# Sheet4_LCD_Interface.net
KiCad netlist of a schematic drawn in Altium Designer
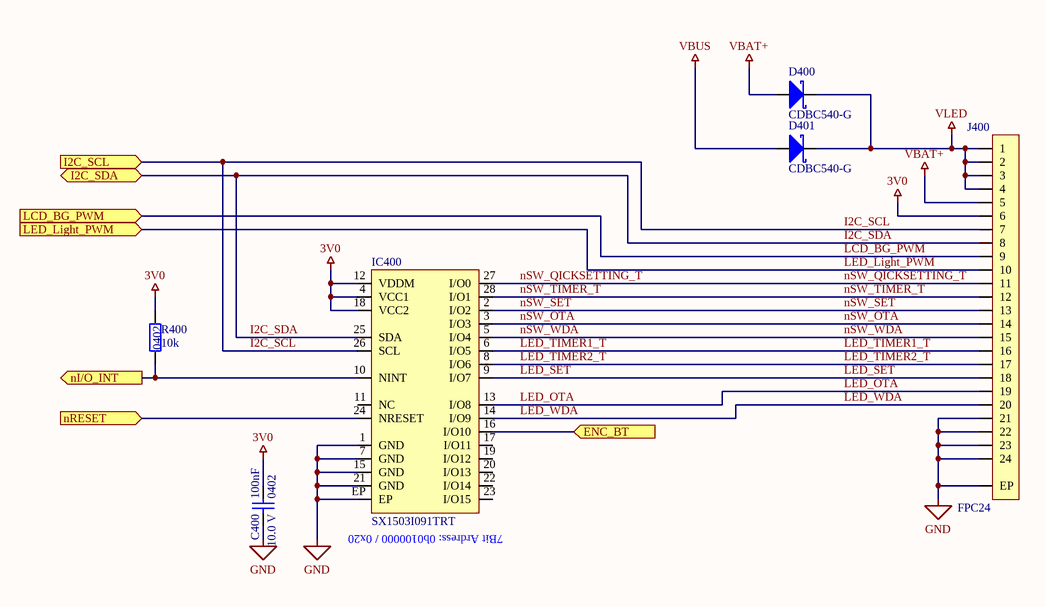
[diagram p0: Sheet4_LCD_Interface.SchDoc]

(export (version "E")
  (design (tool "Eeschema 10.0.6"))
  (components
    (comp (ref "C400")
      (value "C 100nF 0402 10V")
      (footprint "0402")
      (description "CAP CER 0.1UF 10V X5R 0402")
      (fields
        (field (name "MANUFACTURER") "Samsung Electro-Mechanics")
        (field (name "MANUFACTURER PART NUMBER") "CL05A104MP5NNNC")
        (field (name "CAPACITANCE") "100nF")
        (field (name "VOLTAGE") "10.0 V")
      )
      (libsource (lib "CS_Part_Library") (part "CAP_100nF_10V_0402"))
    )
    (comp (ref "D400")
      (value "D SCH 40V 5A")
      (footprint "DO-214AB")
      (description "DIODE SCHOTTKY 40V 5A DO214AB")
      (fields
        (field (name "MANUFACTURER") "Comchip Technology")
        (field (name "MANUFACTURER PART NUMBER") "CDBC540-G")
      )
      (libsource (lib "CS_Part_Library") (part "D_SCH_40V_5A"))
    )
    (comp (ref "D401")
      (value "D SCH 40V 5A")
      (footprint "DO-214AB")
      (description "DIODE SCHOTTKY 40V 5A DO214AB")
      (fields
        (field (name "MANUFACTURER") "Comchip Technology")
        (field (name "MANUFACTURER PART NUMBER") "CDBC540-G")
      )
      (libsource (lib "CS_Part_Library") (part "D_SCH_40V_5A"))
    )
    (comp (ref "IC400")
      (value "SX1503I091TRT")
      (footprint "UFQFN-28-EP")
      (description "IC GPIO EXPANDER I2C 16CH 28-QFN")
      (fields (field (name "MANUFACTURER") "Semtech Corporation"))
      (libsource (lib "CS_Part_Library") (part "IC_16ch_Port_Extender_2"))
    )
    (comp (ref "J400")
      (value "FPC24")
      (footprint "J_FPC_522712479")
      (description "CONN FPC BOT 24 PIN 1mm Pitch")
      (fields (field (name "MANUFACTURER") "MOLEX") (field (name "MANUFACTURER PART NUMBER") "522712479"))
      (libsource (lib "Symbols") (part "J_FPC24_DS"))
    )
    (comp (ref "R400")
      (value "R 10k 0402")
      (footprint "0402")
      (description "RES 10K OHM 1% 1/16W 0402")
      (fields
        (field (name "MANUFACTURER") "YAGEO")
        (field (name "MANUFACTURER PART NUMBER") "RC0402FR-0710KL")
        (field (name "RESISTANCE") "10k")
      )
      (libsource (lib "CS_Part_Library") (part "R_10k_0402"))
    )
  )
  (nets
    (net (code "1") (name "/ENC_BT") (class "Default")
      (node (ref "IC400") (pin "16") (pinfunction "I/O10_16") (pintype "passive"))
    )
    (net (code "2") (name "/I2C_SCL") (class "Default")
      (node (ref "IC400") (pin "26") (pinfunction "SCL_26") (pintype "passive"))
      (node (ref "J400") (pin "7") (pinfunction "7_7") (pintype "passive"))
    )
    (net (code "3") (name "/I2C_SDA") (class "Default")
      (node (ref "IC400") (pin "25") (pinfunction "SDA_25") (pintype "passive"))
      (node (ref "J400") (pin "8") (pinfunction "8_8") (pintype "passive"))
    )
    (net (code "4") (name "/LCD_BG_PWM") (class "Default")
      (node (ref "J400") (pin "9") (pinfunction "9_9") (pintype "passive"))
    )
    (net (code "5") (name "/LED_Light_PWM") (class "Default")
      (node (ref "J400") (pin "10") (pinfunction "10_10") (pintype "passive"))
    )
    (net (code "6") (name "/LED_OTA") (class "Default")
      (node (ref "IC400") (pin "13") (pinfunction "I/O8_13") (pintype "passive"))
      (node (ref "J400") (pin "19") (pinfunction "19_19") (pintype "passive"))
    )
    (net (code "7") (name "/LED_SET") (class "Default")
      (node (ref "IC400") (pin "9") (pinfunction "I/O7_9") (pintype "passive"))
      (node (ref "J400") (pin "18") (pinfunction "18_18") (pintype "passive"))
    )
    (net (code "8") (name "/LED_TIMER1_T") (class "Default")
      (node (ref "IC400") (pin "6") (pinfunction "I/O5_6") (pintype "passive"))
      (node (ref "J400") (pin "16") (pinfunction "16_16") (pintype "passive"))
    )
    (net (code "9") (name "/LED_TIMER2_T") (class "Default")
      (node (ref "IC400") (pin "8") (pinfunction "I/O6_8") (pintype "passive"))
      (node (ref "J400") (pin "17") (pinfunction "17_17") (pintype "passive"))
    )
    (net (code "10") (name "/LED_WDA") (class "Default")
      (node (ref "IC400") (pin "14") (pinfunction "I/O9_14") (pintype "passive"))
      (node (ref "J400") (pin "20") (pinfunction "20_20") (pintype "passive"))
    )
    (net (code "11") (name "/nI{slash}O_INT") (class "Default")
      (node (ref "IC400") (pin "10") (pinfunction "NINT_10") (pintype "passive"))
      (node (ref "R400") (pin "1") (pinfunction "1_1") (pintype "passive"))
    )
    (net (code "12") (name "/nRESET") (class "Default")
      (node (ref "IC400") (pin "24") (pinfunction "NRESET_24") (pintype "passive"))
    )
    (net (code "13") (name "/nSW_OTA") (class "Default")
      (node (ref "IC400") (pin "3") (pinfunction "I/O3_3") (pintype "passive"))
      (node (ref "J400") (pin "14") (pinfunction "14_14") (pintype "passive"))
    )
    (net (code "14") (name "/nSW_QICKSETTING_T") (class "Default")
      (node (ref "IC400") (pin "27") (pinfunction "I/O0_27") (pintype "passive"))
      (node (ref "J400") (pin "11") (pinfunction "11_11") (pintype "passive"))
    )
    (net (code "15") (name "/nSW_SET") (class "Default")
      (node (ref "IC400") (pin "2") (pinfunction "I/O2_2") (pintype "passive"))
      (node (ref "J400") (pin "13") (pinfunction "13_13") (pintype "passive"))
    )
    (net (code "16") (name "/nSW_TIMER_T") (class "Default")
      (node (ref "IC400") (pin "28") (pinfunction "I/O1_28") (pintype "passive"))
      (node (ref "J400") (pin "12") (pinfunction "12_12") (pintype "passive"))
    )
    (net (code "17") (name "/nSW_WDA") (class "Default")
      (node (ref "IC400") (pin "5") (pinfunction "I/O4_5") (pintype "passive"))
      (node (ref "J400") (pin "15") (pinfunction "15_15") (pintype "passive"))
    )
    (net (code "18") (name "3V0") (class "Default")
      (node (ref "C400") (pin "2") (pinfunction "2_2") (pintype "passive"))
      (node (ref "IC400") (pin "12") (pinfunction "VDDM_12") (pintype "passive"))
      (node (ref "IC400") (pin "18") (pinfunction "VCC2_18") (pintype "passive"))
      (node (ref "IC400") (pin "4") (pinfunction "VCC1_4") (pintype "passive"))
      (node (ref "J400") (pin "6") (pinfunction "6_6") (pintype "passive"))
      (node (ref "R400") (pin "2") (pinfunction "2_2") (pintype "passive"))
    )
    (net (code "19") (name "GND") (class "Default")
      (node (ref "C400") (pin "1") (pinfunction "1_1") (pintype "passive"))
      (node (ref "IC400") (pin "1") (pinfunction "GND_1") (pintype "passive"))
      (node (ref "IC400") (pin "15") (pinfunction "GND_15") (pintype "passive"))
      (node (ref "IC400") (pin "21") (pinfunction "GND_21") (pintype "passive"))
      (node (ref "IC400") (pin "7") (pinfunction "GND_7") (pintype "passive"))
      (node (ref "IC400") (pin "EP") (pinfunction "EP_EP") (pintype "passive"))
      (node (ref "J400") (pin "21") (pinfunction "21_21") (pintype "passive"))
      (node (ref "J400") (pin "22") (pinfunction "22_22") (pintype "passive"))
      (node (ref "J400") (pin "23") (pinfunction "23_23") (pintype "passive"))
      (node (ref "J400") (pin "24") (pinfunction "24_24") (pintype "passive"))
      (node (ref "J400") (pin "EP") (pinfunction "EP_EP") (pintype "passive"))
    )
    (net (code "20") (name "VBAT+") (class "Default")
      (node (ref "D400") (pin "2") (pinfunction "A_2") (pintype "passive"))
      (node (ref "J400") (pin "5") (pinfunction "5_5") (pintype "passive"))
    )
    (net (code "21") (name "VBUS") (class "Default")
      (node (ref "D401") (pin "2") (pinfunction "A_2") (pintype "passive"))
    )
    (net (code "22") (name "VLED") (class "Default")
      (node (ref "D400") (pin "1") (pinfunction "K_1") (pintype "passive"))
      (node (ref "D401") (pin "1") (pinfunction "K_1") (pintype "passive"))
      (node (ref "J400") (pin "1") (pinfunction "1_1") (pintype "passive"))
      (node (ref "J400") (pin "2") (pinfunction "2_2") (pintype "passive"))
      (node (ref "J400") (pin "3") (pinfunction "3_3") (pintype "passive"))
      (node (ref "J400") (pin "4") (pinfunction "4_4") (pintype "passive"))
    )
    (net (code "23") (name "unconnected-(IC400-I{slash}O11-Pad17)") (class "Default")
      (node (ref "IC400") (pin "17") (pinfunction "I/O11_17") (pintype "passive"))
    )
    (net (code "24") (name "unconnected-(IC400-I{slash}O12-Pad19)") (class "Default")
      (node (ref "IC400") (pin "19") (pinfunction "I/O12_19") (pintype "passive"))
    )
    (net (code "25") (name "unconnected-(IC400-I{slash}O13-Pad20)") (class "Default")
      (node (ref "IC400") (pin "20") (pinfunction "I/O13_20") (pintype "passive"))
    )
    (net (code "26") (name "unconnected-(IC400-I{slash}O14-Pad22)") (class "Default")
      (node (ref "IC400") (pin "22") (pinfunction "I/O14_22") (pintype "passive"))
    )
    (net (code "27") (name "unconnected-(IC400-I{slash}O15-Pad23)") (class "Default")
      (node (ref "IC400") (pin "23") (pinfunction "I/O15_23") (pintype "passive"))
    )
    (net (code "28") (name "unconnected-(IC400-NC-Pad11)") (class "Default")
      (node (ref "IC400") (pin "11") (pinfunction "NC_11") (pintype "passive"))
    )
  )
)
